# RS232_MAX3232.net
KiCad netlist of a schematic drawn in Altium Designer
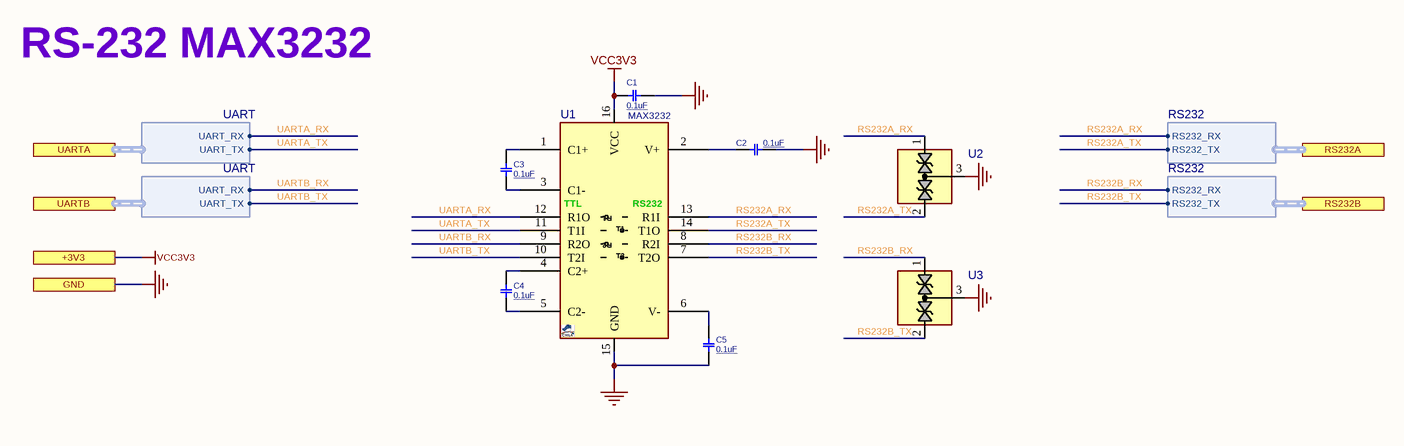
[diagram p0: RS232_MAX3232.SchDoc]

(export (version "E")
  (design (tool "Eeschema 10.0.6"))
  (components
    (comp (ref "C1")
      (value "0.1uF")
      (footprint "C0603")
      (description "CAP, MLCC")
      (fields (field (name "MANF_P#") "MANF_PART#"))
      (libsource (lib "passive_smd") (part "CAP_SMD_MLCC_0402"))
    )
    (comp (ref "C2")
      (value "0.1uF")
      (footprint "C0603")
      (description "CAP, MLCC")
      (fields (field (name "MANF_P#") "MANF_PART#"))
      (libsource (lib "passive_smd") (part "CAP_SMD_MLCC_0402"))
    )
    (comp (ref "C3")
      (value "0.1uF")
      (footprint "C0603")
      (description "CAP, MLCC")
      (fields (field (name "MANF_P#") "MANF_PART#"))
      (libsource (lib "passive_smd") (part "CAP_SMD_MLCC_0402"))
    )
    (comp (ref "C4")
      (value "0.1uF")
      (footprint "C0603")
      (description "CAP, MLCC")
      (fields (field (name "MANF_P#") "MANF_PART#"))
      (libsource (lib "passive_smd") (part "CAP_SMD_MLCC_0402"))
    )
    (comp (ref "C5")
      (value "0.1uF")
      (footprint "C0603")
      (description "CAP, MLCC")
      (fields (field (name "MANF_P#") "MANF_PART#"))
      (libsource (lib "passive_smd") (part "CAP_SMD_MLCC_0402"))
    )
    (comp (ref "U1")
      (value "MAX3232")
      (footprint "SO_16")
      (description "RS-232, DUAL, +3~5V, Driver/Receiver, Low-Power, up to 1Mbps, Using Four 0.1µF External Capacitor")
      (fields (field (name "MANF") "Maxim Integrated") (field (name "MANF_PART#") "MAX3232CSE+"))
      (libsource (lib "rs232") (part "MAX3232_SOP16"))
    )
    (comp (ref "U2")
      (value "CDSOT23-SM712")
      (footprint "SOT23_3")
      (description "TVS, ESD PROTECT, 2CH, 400W/17A PP, 7.5VBR, ±8KV ESDmin")
      (fields (field (name "MANF") "Bourns"))
      (libsource (lib "protect_tvs_esd_fuse") (part "TVS_X2_CDSOT23-SM712"))
    )
    (comp (ref "U3")
      (value "CDSOT23-SM712")
      (footprint "SOT23_3")
      (description "TVS, ESD PROTECT, 2CH, 400W/17A PP, 7.5VBR, ±8KV ESDmin")
      (fields (field (name "MANF") "Bourns"))
      (libsource (lib "protect_tvs_esd_fuse") (part "TVS_X2_CDSOT23-SM712"))
    )
  )
  (nets
    (net (code "3") (name "/RS232A_RX") (class "Default")
      (node (ref "U1") (pin "13") (pinfunction "R1I_13") (pintype "passive"))
      (node (ref "U2") (pin "1") (pinfunction "NC_1") (pintype "passive"))
    )
    (net (code "4") (name "/RS232A_TX") (class "Default")
      (node (ref "U1") (pin "14") (pinfunction "T1O_14") (pintype "passive"))
      (node (ref "U2") (pin "2") (pinfunction "GND_2") (pintype "passive"))
    )
    (net (code "5") (name "/RS232B_RX") (class "Default")
      (node (ref "U1") (pin "8") (pinfunction "R2I_8") (pintype "passive"))
      (node (ref "U3") (pin "1") (pinfunction "NC_1") (pintype "passive"))
    )
    (net (code "6") (name "/RS232B_TX") (class "Default")
      (node (ref "U1") (pin "7") (pinfunction "T2O_7") (pintype "passive"))
      (node (ref "U3") (pin "2") (pinfunction "GND_2") (pintype "passive"))
    )
    (net (code "7") (name "/UARTA_RX") (class "Default")
      (node (ref "U1") (pin "12") (pinfunction "R1O_12") (pintype "passive"))
    )
    (net (code "8") (name "/UARTA_TX") (class "Default")
      (node (ref "U1") (pin "11") (pinfunction "T1I_11") (pintype "passive"))
    )
    (net (code "9") (name "/UARTB_RX") (class "Default")
      (node (ref "U1") (pin "9") (pinfunction "R2O_9") (pintype "passive"))
    )
    (net (code "10") (name "/UARTB_TX") (class "Default")
      (node (ref "U1") (pin "10") (pinfunction "T2I_10") (pintype "passive"))
    )
    (net (code "13") (name "GND") (class "Default")
      (node (ref "C1") (pin "1") (pinfunction "1_1") (pintype "passive"))
      (node (ref "C2") (pin "2") (pinfunction "2_2") (pintype "passive"))
      (node (ref "C5") (pin "2") (pinfunction "2_2") (pintype "passive"))
      (node (ref "U1") (pin "15") (pinfunction "GND_15") (pintype "power_in"))
      (node (ref "U2") (pin "3") (pinfunction "NC_3") (pintype "passive"))
      (node (ref "U3") (pin "3") (pinfunction "NC_3") (pintype "passive"))
    )
    (net (code "14") (name "Net-(U1-C1+)") (class "Default")
      (node (ref "C3") (pin "1") (pinfunction "1_1") (pintype "passive"))
      (node (ref "U1") (pin "1") (pinfunction "C1+_1") (pintype "passive"))
    )
    (net (code "15") (name "Net-(U1-C1-)") (class "Default")
      (node (ref "C3") (pin "2") (pinfunction "2_2") (pintype "passive"))
      (node (ref "U1") (pin "3") (pinfunction "C1-_3") (pintype "passive"))
    )
    (net (code "16") (name "Net-(U1-C2+)") (class "Default")
      (node (ref "C4") (pin "1") (pinfunction "1_1") (pintype "passive"))
      (node (ref "U1") (pin "4") (pinfunction "C2+_4") (pintype "passive"))
    )
    (net (code "17") (name "Net-(U1-C2-)") (class "Default")
      (node (ref "C4") (pin "2") (pinfunction "2_2") (pintype "passive"))
      (node (ref "U1") (pin "5") (pinfunction "C2-_5") (pintype "passive"))
    )
    (net (code "18") (name "Net-(U1-V+)") (class "Default")
      (node (ref "C2") (pin "1") (pinfunction "1_1") (pintype "passive"))
      (node (ref "U1") (pin "2") (pinfunction "V+_2") (pintype "passive"))
    )
    (net (code "19") (name "Net-(U1-V-)") (class "Default")
      (node (ref "C5") (pin "1") (pinfunction "1_1") (pintype "passive"))
      (node (ref "U1") (pin "6") (pinfunction "V-_6") (pintype "passive"))
    )
    (net (code "20") (name "VCC3V3") (class "Default")
      (node (ref "C1") (pin "2") (pinfunction "2_2") (pintype "passive"))
      (node (ref "U1") (pin "16") (pinfunction "VCC_16") (pintype "power_in"))
    )
  )
)
